# CAN.net
KiCad netlist of a schematic drawn in Altium Designer
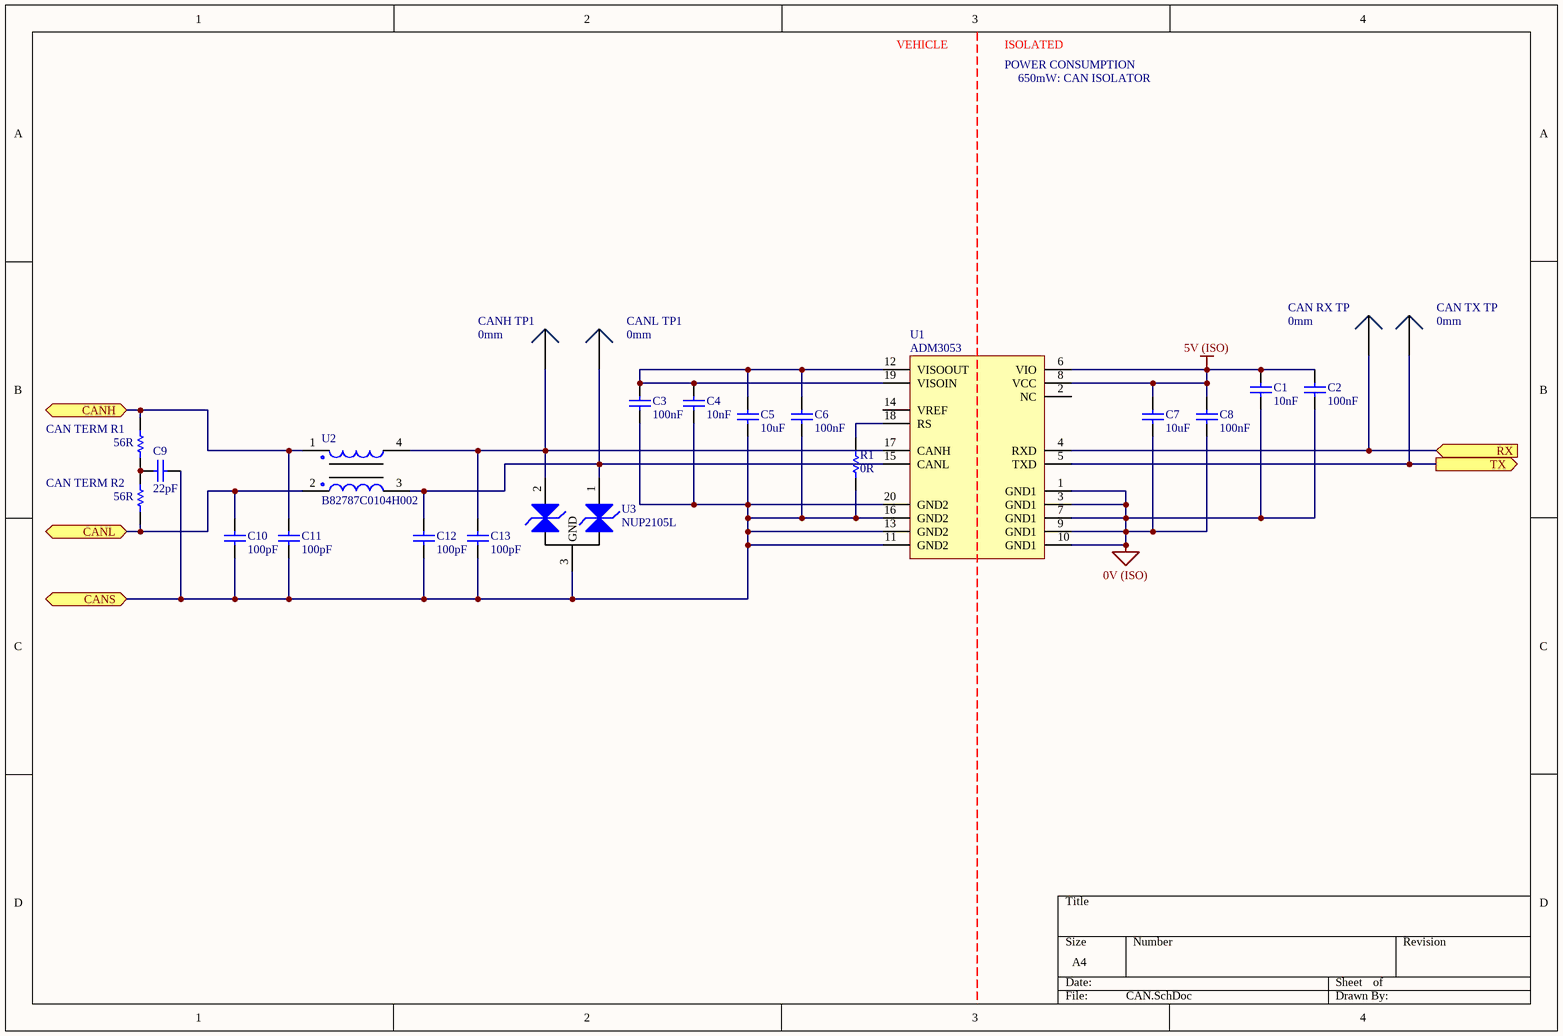
[diagram p0: CAN.SchDoc]

(export (version "E")
  (design (tool "Eeschema 10.0.6"))
  (components
    (comp (ref "C1")
      (value "10nF")
      (footprint "1206")
      (fields
        (field (name "PART NUMBER") "GCM3195C2A103JA16D")
        (field (name "TOLERANCE") "5%")
        (field (name "MANUFACTURER") "muRata")
      )
      (libsource (lib "ts_20-standard-library") (part "Capacitor"))
    )
    (comp (ref "C2")
      (value "100nF")
      (footprint "0805")
      (fields
        (field (name "PART NUMBER") "GCM21BR71E104KA37L")
        (field (name "TOLERANCE") "10%")
        (field (name "MANUFACTURER") "muRata")
      )
      (libsource (lib "ts_20-standard-library") (part "Capacitor"))
    )
    (comp (ref "C3")
      (value "100nF")
      (footprint "0805")
      (fields
        (field (name "PART NUMBER") "GCM21BR71E104KA37L")
        (field (name "TOLERANCE") "10%")
        (field (name "MANUFACTURER") "muRata")
      )
      (libsource (lib "ts_20-standard-library") (part "Capacitor"))
    )
    (comp (ref "C4")
      (value "10nF")
      (footprint "1206")
      (fields
        (field (name "PART NUMBER") "GCM3195C2A103JA16D")
        (field (name "TOLERANCE") "5%")
        (field (name "MANUFACTURER") "muRata")
      )
      (libsource (lib "ts_20-standard-library") (part "Capacitor"))
    )
    (comp (ref "C5")
      (value "10uF")
      (footprint "0805")
      (fields
        (field (name "PART NUMBER") "GRM21BR6YA106KE43L")
        (field (name "TOLERANCE") "10%")
        (field (name "MANUFACTURER") "muRata")
      )
      (libsource (lib "ts_20-standard-library") (part "Capacitor"))
    )
    (comp (ref "C6")
      (value "100nF")
      (footprint "0805")
      (fields
        (field (name "PART NUMBER") "GCM21BR71E104KA37L")
        (field (name "TOLERANCE") "10%")
        (field (name "MANUFACTURER") "muRata")
      )
      (libsource (lib "ts_20-standard-library") (part "Capacitor"))
    )
    (comp (ref "C7")
      (value "10uF")
      (footprint "0805")
      (fields
        (field (name "PART NUMBER") "GRM21BR6YA106KE43L")
        (field (name "TOLERANCE") "10%")
        (field (name "MANUFACTURER") "muRata")
      )
      (libsource (lib "ts_20-standard-library") (part "Capacitor"))
    )
    (comp (ref "C8")
      (value "100nF")
      (footprint "0805")
      (fields
        (field (name "PART NUMBER") "GCM21BR71E104KA37L")
        (field (name "TOLERANCE") "10%")
        (field (name "MANUFACTURER") "muRata")
      )
      (libsource (lib "ts_20-standard-library") (part "Capacitor"))
    )
    (comp (ref "C9")
      (value "22pF")
      (footprint "0805")
      (fields
        (field (name "PART NUMBER") "GCM21B5C1H220JA37L")
        (field (name "TOLERANCE") "5%")
        (field (name "MANUFACTURER") "muRata")
      )
      (libsource (lib "ts_20-standard-library") (part "Capacitor"))
    )
    (comp (ref "C10")
      (value "100pF")
      (footprint "0805")
      (fields
        (field (name "PART NUMBER") "GCM21B5C1H101JA37L")
        (field (name "TOLERANCE") "5%")
        (field (name "MANUFACTURER") "muRata")
      )
      (libsource (lib "ts_20-standard-library") (part "Capacitor"))
    )
    (comp (ref "C11")
      (value "100pF")
      (footprint "0805")
      (fields
        (field (name "PART NUMBER") "GCM21B5C1H101JA37L")
        (field (name "TOLERANCE") "5%")
        (field (name "MANUFACTURER") "muRata")
      )
      (libsource (lib "ts_20-standard-library") (part "Capacitor"))
    )
    (comp (ref "C12")
      (value "100pF")
      (footprint "0805")
      (fields
        (field (name "PART NUMBER") "GCM21B5C1H101JA37L")
        (field (name "TOLERANCE") "5%")
        (field (name "MANUFACTURER") "muRata")
      )
      (libsource (lib "ts_20-standard-library") (part "Capacitor"))
    )
    (comp (ref "C13")
      (value "100pF")
      (footprint "0805")
      (fields
        (field (name "PART NUMBER") "GCM21B5C1H101JA37L")
        (field (name "TOLERANCE") "5%")
        (field (name "MANUFACTURER") "muRata")
      )
      (libsource (lib "ts_20-standard-library") (part "Capacitor"))
    )
    (comp (ref "CAN RX TP")
      (value "0mm")
      (footprint "SMD Test Point")
      (fields (field (name "PART NUMBER") "SMD Test Point") (field (name "CONTACT") "NA"))
      (libsource (lib "ts_20-standard-connectors") (part "Test Point"))
    )
    (comp (ref "CAN TERM R1")
      (value "56R")
      (footprint "0805")
      (fields
        (field (name "PART NUMBER") "RC0805FR0756RL")
        (field (name "MANUFACTURER") "YAGEO")
        (field (name "TOLERANCE") "0.01")
      )
      (libsource (lib "ts_20-standard-library") (part "Resistor"))
    )
    (comp (ref "CAN TERM R2")
      (value "56R")
      (footprint "0805")
      (fields
        (field (name "PART NUMBER") "RC0805FR0756RL")
        (field (name "MANUFACTURER") "YAGEO")
        (field (name "TOLERANCE") "0.01")
      )
      (libsource (lib "ts_20-standard-library") (part "Resistor"))
    )
    (comp (ref "CAN TX TP")
      (value "0mm")
      (footprint "SMD Test Point")
      (fields (field (name "PART NUMBER") "SMD Test Point") (field (name "CONTACT") "NA"))
      (libsource (lib "ts_20-standard-connectors") (part "Test Point"))
    )
    (comp (ref "CANH TP1")
      (value "0mm")
      (footprint "SMD Test Point")
      (fields (field (name "PART NUMBER") "SMD Test Point") (field (name "CONTACT") "NA"))
      (libsource (lib "ts_20-standard-connectors") (part "Test Point"))
    )
    (comp (ref "CANL TP1")
      (value "0mm")
      (footprint "SMD Test Point")
      (fields (field (name "PART NUMBER") "SMD Test Point") (field (name "CONTACT") "NA"))
      (libsource (lib "ts_20-standard-connectors") (part "Test Point"))
    )
    (comp (ref "R1")
      (value "0R")
      (footprint "0805")
      (fields
        (field (name "PART NUMBER") "RC0805FR070RL")
        (field (name "MANUFACTURER") "YAGEO")
        (field (name "TOLERANCE") "0.01")
      )
      (libsource (lib "ts_20-standard-library") (part "Resistor"))
    )
    (comp (ref "U1")
      (value "ADM3053")
      (footprint "AD SOIC-W 20")
      (description "Isolated CAN Transceiver")
      (fields
        (field (name "MANUFACTURER") "Analogue Devices")
        (field (name "DIGIKEY PART NUMBER") "ADM3053BRWZ-ND")
      )
      (libsource (lib "ts_20-standard-library") (part "ADM3053"))
    )
    (comp (ref "U2")
      (value "B82787C0104H002")
      (footprint "TDK 4-PC Pad")
      (description "100µH @ 100kHz 2 Line Common Mode Choke Surface Mount 5.8 kOhms @ 10MHz 150mA DCR 2Ohm")
      (fields
        (field (name "MANUFACTURER") "EPCOS (TDK)")
        (field (name "DIGIKEY PART NUMBER") "495-4598-1-ND")
      )
      (libsource (lib "ts_20-standard-library") (part "B82787C0104H002"))
    )
    (comp (ref "U3")
      (value "NUP2105L")
      (footprint "ON SOT-23")
      (description "Dual Line CAN Bus Protector")
      (fields
        (field (name "MANUFACTURER") "ON Semiconductor")
        (field (name "DIGIKEY PART NUMBER") "NUP2105LT1GOSCT-ND")
      )
      (libsource (lib "ts_20-standard-library") (part "NUP2105L"))
    )
  )
  (nets
    (net (code "1") (name "/CANH") (class "Default")
      (node (ref "C11") (pin "2") (pinfunction "2_2") (pintype "passive"))
      (node (ref "CAN TERM R1") (pin "2") (pinfunction "2_2") (pintype "passive"))
      (node (ref "U2") (pin "1") (pinfunction "1_1") (pintype "passive"))
    )
    (net (code "2") (name "/CANL") (class "Default")
      (node (ref "C10") (pin "2") (pinfunction "2_2") (pintype "passive"))
      (node (ref "CAN TERM R2") (pin "1") (pinfunction "1_1") (pintype "passive"))
      (node (ref "U2") (pin "2") (pinfunction "2_2") (pintype "passive"))
    )
    (net (code "3") (name "/CANS") (class "Default")
      (node (ref "C10") (pin "1") (pinfunction "1_1") (pintype "passive"))
      (node (ref "C11") (pin "1") (pinfunction "1_1") (pintype "passive"))
      (node (ref "C12") (pin "1") (pinfunction "1_1") (pintype "passive"))
      (node (ref "C13") (pin "1") (pinfunction "1_1") (pintype "passive"))
      (node (ref "C3") (pin "1") (pinfunction "1_1") (pintype "passive"))
      (node (ref "C4") (pin "1") (pinfunction "1_1") (pintype "passive"))
      (node (ref "C5") (pin "1") (pinfunction "1_1") (pintype "passive"))
      (node (ref "C6") (pin "1") (pinfunction "1_1") (pintype "passive"))
      (node (ref "C9") (pin "1") (pinfunction "1_1") (pintype "passive"))
      (node (ref "R1") (pin "1") (pinfunction "1_1") (pintype "passive"))
      (node (ref "U1") (pin "11") (pinfunction "GND2_11") (pintype "passive"))
      (node (ref "U1") (pin "13") (pinfunction "GND2_13") (pintype "passive"))
      (node (ref "U1") (pin "16") (pinfunction "GND2_16") (pintype "passive"))
      (node (ref "U1") (pin "20") (pinfunction "GND2_20") (pintype "passive"))
      (node (ref "U3") (pin "3") (pinfunction "GND_3") (pintype "power_in"))
    )
    (net (code "4") (name "/RX") (class "Default")
      (node (ref "CAN RX TP") (pin "1") (pinfunction "1_1") (pintype "passive"))
      (node (ref "U1") (pin "4") (pinfunction "RXD_4") (pintype "passive"))
    )
    (net (code "5") (name "/TX") (class "Default")
      (node (ref "CAN TX TP") (pin "1") (pinfunction "1_1") (pintype "passive"))
      (node (ref "U1") (pin "5") (pinfunction "TXD_5") (pintype "passive"))
    )
    (net (code "6") (name "0V (ISO)") (class "Default")
      (node (ref "C1") (pin "1") (pinfunction "1_1") (pintype "passive"))
      (node (ref "C2") (pin "1") (pinfunction "1_1") (pintype "passive"))
      (node (ref "C7") (pin "1") (pinfunction "1_1") (pintype "passive"))
      (node (ref "C8") (pin "1") (pinfunction "1_1") (pintype "passive"))
      (node (ref "U1") (pin "1") (pinfunction "GND1_1") (pintype "passive"))
      (node (ref "U1") (pin "10") (pinfunction "GND1_10") (pintype "passive"))
      (node (ref "U1") (pin "3") (pinfunction "GND1_3") (pintype "passive"))
      (node (ref "U1") (pin "7") (pinfunction "GND1_7") (pintype "passive"))
      (node (ref "U1") (pin "9") (pinfunction "GND1_9") (pintype "passive"))
    )
    (net (code "7") (name "5V (ISO)") (class "Default")
      (node (ref "C1") (pin "2") (pinfunction "2_2") (pintype "passive"))
      (node (ref "C2") (pin "2") (pinfunction "2_2") (pintype "passive"))
      (node (ref "C7") (pin "2") (pinfunction "2_2") (pintype "passive"))
      (node (ref "C8") (pin "2") (pinfunction "2_2") (pintype "passive"))
      (node (ref "U1") (pin "6") (pinfunction "VIO_6") (pintype "passive"))
      (node (ref "U1") (pin "8") (pinfunction "VCC_8") (pintype "passive"))
    )
    (net (code "8") (name "Net-(C9-Pad2)") (class "Default")
      (node (ref "C9") (pin "2") (pinfunction "2_2") (pintype "passive"))
      (node (ref "CAN TERM R1") (pin "1") (pinfunction "1_1") (pintype "passive"))
      (node (ref "CAN TERM R2") (pin "2") (pinfunction "2_2") (pintype "passive"))
    )
    (net (code "9") (name "Net-(U1-CANH)") (class "Default")
      (node (ref "C13") (pin "2") (pinfunction "2_2") (pintype "passive"))
      (node (ref "CANH TP1") (pin "1") (pinfunction "1_1") (pintype "passive"))
      (node (ref "U1") (pin "17") (pinfunction "CANH_17") (pintype "passive"))
      (node (ref "U2") (pin "4") (pinfunction "4_4") (pintype "passive"))
      (node (ref "U3") (pin "2") (pinfunction "CAN_L_2") (pintype "passive"))
    )
    (net (code "10") (name "Net-(U1-CANL)") (class "Default")
      (node (ref "C12") (pin "2") (pinfunction "2_2") (pintype "passive"))
      (node (ref "CANL TP1") (pin "1") (pinfunction "1_1") (pintype "passive"))
      (node (ref "U1") (pin "15") (pinfunction "CANL_15") (pintype "passive"))
      (node (ref "U2") (pin "3") (pinfunction "3_3") (pintype "power_in"))
      (node (ref "U3") (pin "1") (pinfunction "CAN_H_1") (pintype "passive"))
    )
    (net (code "11") (name "Net-(U1-RS)") (class "Default")
      (node (ref "R1") (pin "2") (pinfunction "2_2") (pintype "passive"))
      (node (ref "U1") (pin "18") (pinfunction "RS_18") (pintype "passive"))
    )
    (net (code "12") (name "Net-(U1-VISOIN)") (class "Default")
      (node (ref "C3") (pin "2") (pinfunction "2_2") (pintype "passive"))
      (node (ref "C4") (pin "2") (pinfunction "2_2") (pintype "passive"))
      (node (ref "C5") (pin "2") (pinfunction "2_2") (pintype "passive"))
      (node (ref "C6") (pin "2") (pinfunction "2_2") (pintype "passive"))
      (node (ref "U1") (pin "12") (pinfunction "VISOOUT_12") (pintype "passive"))
      (node (ref "U1") (pin "19") (pinfunction "VISOIN_19") (pintype "passive"))
    )
    (net (code "13") (name "unconnected-(U1-NC-Pad2)") (class "Default")
      (node (ref "U1") (pin "2") (pinfunction "NC_2") (pintype "passive"))
    )
    (net (code "14") (name "unconnected-(U1-VREF-Pad14)") (class "Default")
      (node (ref "U1") (pin "14") (pinfunction "VREF_14") (pintype "passive"))
    )
  )
)
